# RS485_IF.net
KiCad netlist of a schematic drawn in Altium Designer
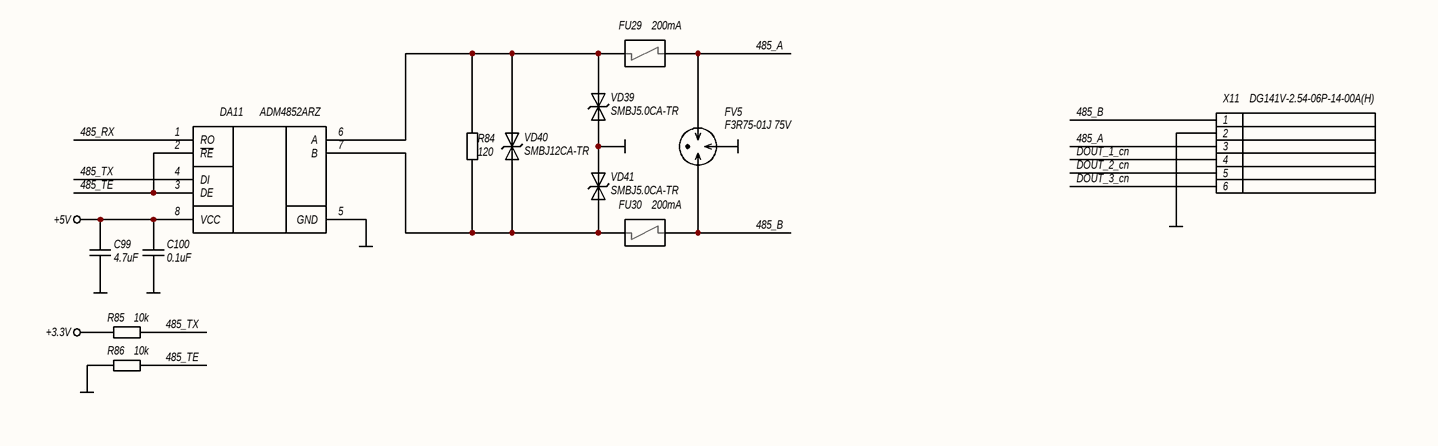
[diagram p0: RS485_IF.SchDoc]

(export (version "E")
  (design (tool "Eeschema 10.0.6"))
  (components
    (comp (ref "C99")
      (value "4.7uF")
      (footprint "C0603N")
      (description "Конденсатор")
      (libsource (lib "Components Library") (part "CAP_FIXED"))
    )
    (comp (ref "C100")
      (value "0.1uF")
      (footprint "C0603N")
      (description "Конденсатор")
      (libsource (lib "Components Library") (part "CAP_FIXED"))
    )
    (comp (ref "DA11")
      (value "ADM4852ARZ")
      (footprint "SOIC8")
      (description "Микросхема интерфейса RS485")
      (libsource (lib "Components Library") (part "ADM4852A"))
    )
    (comp (ref "FU29")
      (value "200mA")
      (footprint "TBU-CA")
      (description "Полупроводниковый предохранитель")
      (libsource (lib "Components Library") (part "FUSE_TBU"))
    )
    (comp (ref "FU30")
      (value "200mA")
      (footprint "TBU-CA")
      (description "Полупроводниковый предохранитель")
      (libsource (lib "Components Library") (part "FUSE_TBU"))
    )
    (comp (ref "FV5")
      (value "F3R75-01J 75V")
      (footprint "GDT_3PIN_B2")
      (description "Газовый разрядник, трехвыводный")
      (libsource (lib "Components Library") (part "GDT_3PIN"))
    )
    (comp (ref "R84")
      (value "120")
      (footprint "R0805N")
      (description "Резистор")
      (libsource (lib "") (part "RES_FIXED_1"))
    )
    (comp (ref "R85")
      (value "10k")
      (footprint "R0603N")
      (description "Резистор")
      (libsource (lib "Components Library") (part "RES_FIXED"))
    )
    (comp (ref "R86")
      (value "10k")
      (footprint "R0603N")
      (description "Резистор")
      (libsource (lib "Components Library") (part "RES_FIXED"))
    )
    (comp (ref "VD39")
      (value "SMBJ5.0CA-TR")
      (footprint "SMB")
      (description "TVS диод двунаправленный")
      (libsource (lib "Components Library") (part "TVS_BIDIR"))
    )
    (comp (ref "VD40")
      (value "SMBJ12CA-TR")
      (footprint "SMB")
      (description "TVS диод двунаправленный")
      (libsource (lib "Components Library") (part "TVS_BIDIR"))
    )
    (comp (ref "VD41")
      (value "SMBJ5.0CA-TR")
      (footprint "SMB")
      (description "TVS диод двунаправленный")
      (libsource (lib "Components Library") (part "TVS_BIDIR"))
    )
    (comp (ref "X11")
      (value "DG141V-2.54-06P-14-00A(H)")
      (footprint "DG141V-2.54-06P-14-00A(H)")
      (description "Разъем, 6 контактов")
      (libsource (lib "Components Library") (part "Connector 6"))
    )
  )
  (nets
    (net (code "1") (name "+3.3V") (class "Default")
      (node (ref "R85") (pin "2") (pinfunction "2_2") (pintype "passive"))
    )
    (net (code "2") (name "+5V") (class "Default")
      (node (ref "C100") (pin "2") (pinfunction "2_2") (pintype "passive"))
      (node (ref "C99") (pin "2") (pinfunction "2_2") (pintype "passive"))
      (node (ref "DA11") (pin "8") (pinfunction "VCC_8") (pintype "power_in"))
    )
    (net (code "3") (name "/485_A") (class "Default")
      (node (ref "FU29") (pin "3") (pinfunction "IN/OUT_3") (pintype "passive"))
      (node (ref "FV5") (pin "3") (pinfunction "3_3") (pintype "passive"))
      (node (ref "X11") (pin "3") (pinfunction "3_3") (pintype "power_in"))
    )
    (net (code "4") (name "/485_B") (class "Default")
      (node (ref "FU30") (pin "3") (pinfunction "IN/OUT_3") (pintype "passive"))
      (node (ref "FV5") (pin "1") (pinfunction "1_1") (pintype "passive"))
      (node (ref "X11") (pin "1") (pinfunction "1_1") (pintype "power_in"))
    )
    (net (code "5") (name "/485_RX") (class "Default")
      (node (ref "DA11") (pin "1") (pinfunction "RO_1") (pintype "power_in"))
    )
    (net (code "6") (name "/485_TE") (class "Default")
      (node (ref "DA11") (pin "2") (pinfunction "~{RE}_2") (pintype "power_in"))
      (node (ref "DA11") (pin "3") (pinfunction "DE_3") (pintype "power_in"))
      (node (ref "R86") (pin "1") (pinfunction "1_1") (pintype "passive"))
    )
    (net (code "7") (name "/485_TX") (class "Default")
      (node (ref "DA11") (pin "4") (pinfunction "DI_4") (pintype "power_in"))
      (node (ref "R85") (pin "1") (pinfunction "1_1") (pintype "passive"))
    )
    (net (code "8") (name "/DOUT_1_cn") (class "Default")
      (node (ref "X11") (pin "4") (pinfunction "4_4") (pintype "power_in"))
    )
    (net (code "9") (name "/DOUT_2_cn") (class "Default")
      (node (ref "X11") (pin "5") (pinfunction "5_5") (pintype "power_in"))
    )
    (net (code "10") (name "/DOUT_3_cn") (class "Default")
      (node (ref "X11") (pin "6") (pinfunction "6_6") (pintype "power_in"))
    )
    (net (code "11") (name "GND") (class "Default")
      (node (ref "C100") (pin "1") (pinfunction "1_1") (pintype "passive"))
      (node (ref "C99") (pin "1") (pinfunction "1_1") (pintype "passive"))
      (node (ref "DA11") (pin "5") (pinfunction "GND_5") (pintype "power_in"))
      (node (ref "FV5") (pin "2") (pinfunction "2_2") (pintype "passive"))
      (node (ref "R86") (pin "2") (pinfunction "2_2") (pintype "passive"))
      (node (ref "VD39") (pin "2") (pinfunction "A2_2") (pintype "passive"))
      (node (ref "VD41") (pin "2") (pinfunction "A2_2") (pintype "passive"))
      (node (ref "X11") (pin "2") (pinfunction "2_2") (pintype "power_in"))
    )
    (net (code "12") (name "Net-(DA11-A)") (class "Default")
      (node (ref "DA11") (pin "6") (pinfunction "A_6") (pintype "power_in"))
      (node (ref "FU29") (pin "1") (pinfunction "IN/OUT_1") (pintype "passive"))
      (node (ref "R84") (pin "2") (pinfunction "2_2") (pintype "passive"))
      (node (ref "VD39") (pin "1") (pinfunction "A1_1") (pintype "passive"))
      (node (ref "VD40") (pin "2") (pinfunction "A2_2") (pintype "passive"))
    )
    (net (code "13") (name "Net-(DA11-B)") (class "Default")
      (node (ref "DA11") (pin "7") (pinfunction "B_7") (pintype "power_in"))
      (node (ref "FU30") (pin "1") (pinfunction "IN/OUT_1") (pintype "passive"))
      (node (ref "R84") (pin "1") (pinfunction "1_1") (pintype "passive"))
      (node (ref "VD40") (pin "1") (pinfunction "A1_1") (pintype "passive"))
      (node (ref "VD41") (pin "1") (pinfunction "A1_1") (pintype "passive"))
    )
  )
)
